# RF_ADF.net
KiCad netlist of a schematic drawn in Altium Designer
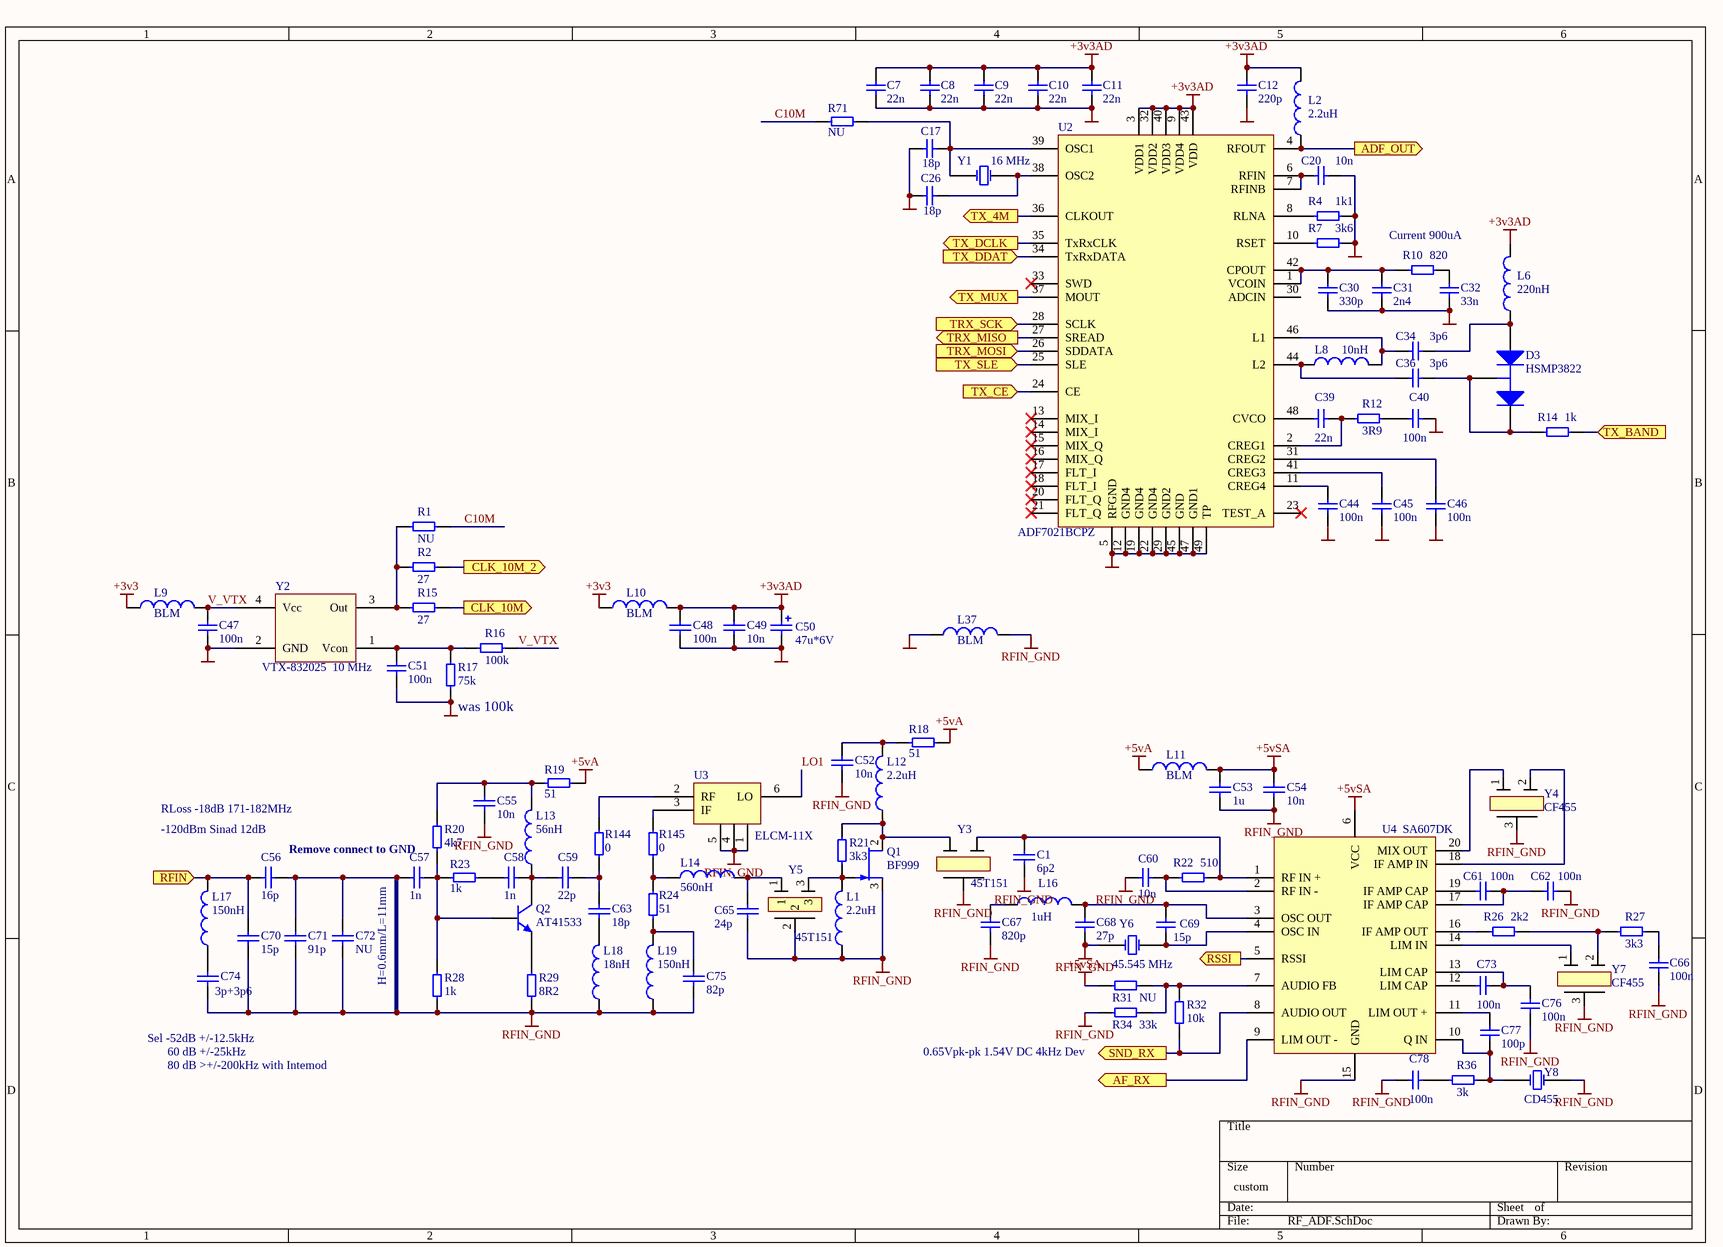
[diagram p0: RF_ADF.SchDoc]

(export (version "E")
  (design (tool "Eeschema 10.0.6"))
  (components
    (comp (ref "C1")
      (value "6p2")
      (footprint "CAPC2012N")
      (description "Capacitor")
      (fields (field (name "PUBLISHER") "Altium Limited"))
      (libsource (lib "Sch components") (part "Cap"))
    )
    (comp (ref "C7")
      (value "22n")
      (footprint "CAPC1608L")
      (description "Capacitor")
      (fields (field (name "PUBLISHER") "Altium Limited"))
      (libsource (lib "") (part "Cap_1"))
    )
    (comp (ref "C8")
      (value "22n")
      (footprint "CAPC1608L")
      (description "Capacitor")
      (fields (field (name "PUBLISHER") "Altium Limited"))
      (libsource (lib "") (part "Cap_1"))
    )
    (comp (ref "C9")
      (value "22n")
      (footprint "CAPC1608L")
      (description "Capacitor")
      (fields (field (name "PUBLISHER") "Altium Limited"))
      (libsource (lib "") (part "Cap_1"))
    )
    (comp (ref "C10")
      (value "22n")
      (footprint "CAPC1608L")
      (description "Capacitor")
      (fields (field (name "PUBLISHER") "Altium Limited"))
      (libsource (lib "") (part "Cap_1"))
    )
    (comp (ref "C11")
      (value "22n")
      (footprint "CAPC1608L")
      (description "Capacitor")
      (fields (field (name "PUBLISHER") "Altium Limited"))
      (libsource (lib "") (part "Cap_1"))
    )
    (comp (ref "C12")
      (value "220p")
      (footprint "CAPC1608L")
      (description "Capacitor")
      (fields (field (name "PUBLISHER") "Altium Limited"))
      (libsource (lib "") (part "Cap_1"))
    )
    (comp (ref "C17")
      (value "18p")
      (footprint "CAPC1608L")
      (description "Capacitor")
      (fields (field (name "PUBLISHER") "Altium Limited"))
      (libsource (lib "") (part "Cap_1"))
    )
    (comp (ref "C20")
      (value "10n")
      (footprint "CAPC1608L")
      (description "Capacitor")
      (fields (field (name "PUBLISHER") "Altium Limited"))
      (libsource (lib "") (part "Cap_1"))
    )
    (comp (ref "C26")
      (value "18p")
      (footprint "CAPC1608L")
      (description "Capacitor")
      (fields (field (name "PUBLISHER") "Altium Limited"))
      (libsource (lib "") (part "Cap_1"))
    )
    (comp (ref "C30")
      (value "330p")
      (footprint "CAPC1608L")
      (description "Capacitor")
      (fields (field (name "PUBLISHER") "Altium Limited"))
      (libsource (lib "") (part "Cap_1"))
    )
    (comp (ref "C31")
      (value "2n4")
      (footprint "CAPC1608L")
      (description "Capacitor")
      (fields (field (name "PUBLISHER") "Altium Limited"))
      (libsource (lib "") (part "Cap_1"))
    )
    (comp (ref "C32")
      (value "33n")
      (footprint "CAPC1608L")
      (description "Capacitor")
      (fields (field (name "PUBLISHER") "Altium Limited"))
      (libsource (lib "") (part "Cap_1"))
    )
    (comp (ref "C34")
      (value "3p6")
      (footprint "CAPC1608L")
      (description "Capacitor")
      (fields (field (name "PUBLISHER") "Altium Limited"))
      (libsource (lib "") (part "Cap_1"))
    )
    (comp (ref "C36")
      (value "3p6")
      (footprint "CAPC1608L")
      (description "Capacitor")
      (fields (field (name "PUBLISHER") "Altium Limited"))
      (libsource (lib "") (part "Cap_1"))
    )
    (comp (ref "C39")
      (value "22n")
      (footprint "CAPC1608L")
      (description "Capacitor")
      (fields (field (name "PUBLISHER") "Altium Limited"))
      (libsource (lib "") (part "Cap_1"))
    )
    (comp (ref "C40")
      (value "100n")
      (footprint "CAPC1608L")
      (description "Capacitor")
      (fields (field (name "PUBLISHER") "Altium Limited"))
      (libsource (lib "") (part "Cap_1"))
    )
    (comp (ref "C44")
      (value "100n")
      (footprint "CAPC1608L")
      (description "Capacitor")
      (fields (field (name "PUBLISHER") "Altium Limited"))
      (libsource (lib "") (part "Cap_1"))
    )
    (comp (ref "C45")
      (value "100n")
      (footprint "CAPC1608L")
      (description "Capacitor")
      (fields (field (name "PUBLISHER") "Altium Limited"))
      (libsource (lib "") (part "Cap_1"))
    )
    (comp (ref "C46")
      (value "100n")
      (footprint "CAPC1608L")
      (description "Capacitor")
      (fields (field (name "PUBLISHER") "Altium Limited"))
      (libsource (lib "") (part "Cap_1"))
    )
    (comp (ref "C47")
      (value "100n")
      (footprint "CAPC1608L")
      (description "Capacitor")
      (fields (field (name "PUBLISHER") "Altium Limited"))
      (libsource (lib "") (part "Cap_1"))
    )
    (comp (ref "C48")
      (value "100n")
      (footprint "CAPC1608N")
      (description "Capacitor")
      (fields (field (name "PUBLISHER") "Altium Limited"))
      (libsource (lib "Sch components") (part "Cap"))
    )
    (comp (ref "C49")
      (value "10n")
      (footprint "CAPC1608N")
      (description "Capacitor")
      (fields (field (name "PUBLISHER") "Altium Limited"))
      (libsource (lib "Sch components") (part "Cap"))
    )
    (comp (ref "C50")
      (value "47u*6V")
      (footprint "Case_A")
      (description "Polarized Capacitor (Surface Mount)")
      (fields (field (name "PUBLISHER") "Altium Limited"))
      (libsource (lib "Sch components") (part "Cap Pol"))
    )
    (comp (ref "C51")
      (value "100n")
      (footprint "CAPC1608L")
      (description "Capacitor")
      (fields (field (name "PUBLISHER") "Altium Limited"))
      (libsource (lib "") (part "Cap_1"))
    )
    (comp (ref "C52")
      (value "10n")
      (footprint "CAPC2012N")
      (description "Capacitor")
      (fields (field (name "PUBLISHER") "Altium Limited"))
      (libsource (lib "Sch components") (part "Cap"))
    )
    (comp (ref "C53")
      (value "1u")
      (footprint "CAPC2012L")
      (description "Capacitor")
      (fields (field (name "PUBLISHER") "Altium Limited"))
      (libsource (lib "Sch components") (part "Cap"))
    )
    (comp (ref "C54")
      (value "10n")
      (footprint "CAPC1608L")
      (description "Capacitor")
      (fields (field (name "PUBLISHER") "Altium Limited"))
      (libsource (lib "Sch components") (part "Cap"))
    )
    (comp (ref "C55")
      (value "10n")
      (footprint "CAPC2012N")
      (description "Capacitor")
      (fields (field (name "PUBLISHER") "Altium Limited"))
      (libsource (lib "Sch components") (part "Cap"))
    )
    (comp (ref "C56")
      (value "16p")
      (footprint "CAPC2012N")
      (description "Capacitor")
      (fields (field (name "PUBLISHER") "Altium Limited"))
      (libsource (lib "Sch components") (part "Cap"))
    )
    (comp (ref "C57")
      (value "1n")
      (footprint "CAPC2012N")
      (description "Capacitor")
      (fields (field (name "PUBLISHER") "Altium Limited"))
      (libsource (lib "Sch components") (part "Cap"))
    )
    (comp (ref "C58")
      (value "1n")
      (footprint "CAPC2012N")
      (description "Capacitor")
      (fields (field (name "PUBLISHER") "Altium Limited"))
      (libsource (lib "Sch components") (part "Cap"))
    )
    (comp (ref "C59")
      (value "22p")
      (footprint "CAPC2012N")
      (description "Capacitor")
      (fields (field (name "PUBLISHER") "Altium Limited"))
      (libsource (lib "Sch components") (part "Cap"))
    )
    (comp (ref "C60")
      (value "10n")
      (footprint "CAPC1608L")
      (description "Capacitor")
      (fields (field (name "PUBLISHER") "Altium Limited"))
      (libsource (lib "") (part "Cap_1"))
    )
    (comp (ref "C61")
      (value "100n")
      (footprint "CAPC1608L")
      (description "Capacitor")
      (fields (field (name "PUBLISHER") "Altium Limited"))
      (libsource (lib "") (part "Cap_1"))
    )
    (comp (ref "C62")
      (value "100n")
      (footprint "CAPC1608L")
      (description "Capacitor")
      (fields (field (name "PUBLISHER") "Altium Limited"))
      (libsource (lib "") (part "Cap_1"))
    )
    (comp (ref "C63")
      (value "18p")
      (footprint "CAPC2012N")
      (description "Capacitor")
      (fields (field (name "PUBLISHER") "Altium Limited"))
      (libsource (lib "Sch components") (part "Cap"))
    )
    (comp (ref "C65")
      (value "24p")
      (footprint "CAPC2012N")
      (description "Capacitor")
      (fields (field (name "PUBLISHER") "Altium Limited"))
      (libsource (lib "Sch components") (part "Cap"))
    )
    (comp (ref "C66")
      (value "100n")
      (footprint "CAPC1608L")
      (description "Capacitor")
      (fields (field (name "PUBLISHER") "Altium Limited"))
      (libsource (lib "") (part "Cap_1"))
    )
    (comp (ref "C67")
      (value "820p")
      (footprint "CAPC1608L")
      (description "Capacitor")
      (fields (field (name "PUBLISHER") "Altium Limited"))
      (libsource (lib "") (part "Cap_1"))
    )
    (comp (ref "C68")
      (value "27p")
      (footprint "CAPC1608L")
      (description "Capacitor")
      (fields (field (name "PUBLISHER") "Altium Limited"))
      (libsource (lib "") (part "Cap_1"))
    )
    (comp (ref "C69")
      (value "15p")
      (footprint "CAPC1608L")
      (description "Capacitor")
      (fields (field (name "PUBLISHER") "Altium Limited"))
      (libsource (lib "") (part "Cap_1"))
    )
    (comp (ref "C70")
      (value "15p")
      (footprint "CAPC2012N")
      (description "Capacitor")
      (fields (field (name "PUBLISHER") "Altium Limited"))
      (libsource (lib "Sch components") (part "Cap"))
    )
    (comp (ref "C71")
      (value "91p")
      (footprint "CAPC2012N")
      (description "Capacitor")
      (fields (field (name "PUBLISHER") "Altium Limited"))
      (libsource (lib "Sch components") (part "Cap"))
    )
    (comp (ref "C72")
      (value "NU")
      (footprint "CAPC2012N")
      (description "Capacitor")
      (fields (field (name "PUBLISHER") "Altium Limited"))
      (libsource (lib "Sch components") (part "Cap"))
    )
    (comp (ref "C73")
      (value "100n")
      (footprint "CAPC1608L")
      (description "Capacitor")
      (fields (field (name "PUBLISHER") "Altium Limited"))
      (libsource (lib "") (part "Cap_1"))
    )
    (comp (ref "C74")
      (value "3p+3p6")
      (footprint "CAPC2012N")
      (description "Capacitor")
      (fields (field (name "PUBLISHER") "Altium Limited"))
      (libsource (lib "Sch components") (part "Cap"))
    )
    (comp (ref "C75")
      (value "82p")
      (footprint "CAPC2012N")
      (description "Capacitor")
      (fields (field (name "PUBLISHER") "Altium Limited"))
      (libsource (lib "Sch components") (part "Cap"))
    )
    (comp (ref "C76")
      (value "100n")
      (footprint "CAPC1608L")
      (description "Capacitor")
      (fields (field (name "PUBLISHER") "Altium Limited"))
      (libsource (lib "") (part "Cap_1"))
    )
    (comp (ref "C77")
      (value "100p")
      (footprint "CAPC1608L")
      (description "Capacitor")
      (fields (field (name "PUBLISHER") "Altium Limited"))
      (libsource (lib "") (part "Cap_1"))
    )
    (comp (ref "C78")
      (value "100n")
      (footprint "CAPC1608L")
      (description "Capacitor")
      (fields (field (name "PUBLISHER") "Altium Limited"))
      (libsource (lib "") (part "Cap_1"))
    )
    (comp (ref "D3")
      (value "HSMP3822")
      (footprint "SOT-23")
      (description "Silicon Switching Diode Array for High-Speed Switching")
      (fields (field (name "PUBLISHER") "Altium Limited"))
      (libsource (lib "Infineon Discrete Diode") (part "SMBD7000"))
    )
    (comp (ref "L1")
      (value "2.2uH")
      (footprint "INDC2012N")
      (description "Inductor")
      (fields (field (name "PUBLISHER") "Altium Limited"))
      (libsource (lib "Sch components") (part "Inductor"))
    )
    (comp (ref "L2") (value "2.2uH") (footprint "INDC2012L") (libsource (lib "MyLibrary") (part "INDUCTOR")))
    (comp (ref "L6") (value "220nH") (footprint "INDC2012L") (libsource (lib "MyLibrary") (part "INDUCTOR")))
    (comp (ref "L8") (value "10nH") (footprint "INDC2012L") (libsource (lib "MyLibrary") (part "INDUCTOR")))
    (comp (ref "L9")
      (value "BLM")
      (footprint "CAPC2012N")
      (description "Ferrite Bead")
      (fields (field (name "PUBLISHER") "Altium Limited"))
      (libsource (lib "Sch components") (part "Ferrite Bead"))
    )
    (comp (ref "L10")
      (value "BLM")
      (footprint "CAPC2012N")
      (description "Ferrite Bead")
      (fields (field (name "PUBLISHER") "Altium Limited"))
      (libsource (lib "Sch components") (part "Ferrite Bead"))
    )
    (comp (ref "L11")
      (value "BLM")
      (footprint "CAPC2012N")
      (description "Ferrite Bead")
      (fields (field (name "PUBLISHER") "Altium Limited"))
      (libsource (lib "Sch components") (part "Ferrite Bead"))
    )
    (comp (ref "L12")
      (value "2.2uH")
      (footprint "INDC2012N")
      (description "Inductor")
      (fields (field (name "PUBLISHER") "Altium Limited"))
      (libsource (lib "Sch components") (part "Inductor"))
    )
    (comp (ref "L13")
      (value "56nH")
      (footprint "INDC2012N")
      (description "Inductor")
      (fields (field (name "PUBLISHER") "Altium Limited"))
      (libsource (lib "Sch components") (part "Inductor"))
    )
    (comp (ref "L14")
      (value "560nH")
      (footprint "INDC2012N")
      (description "Inductor")
      (fields (field (name "PUBLISHER") "Altium Limited"))
      (libsource (lib "Sch components") (part "Inductor"))
    )
    (comp (ref "L16") (value "1uH") (footprint "INDC2012L") (libsource (lib "MyLibrary") (part "INDUCTOR")))
    (comp (ref "L17")
      (value "150nH")
      (footprint "INDC2012N")
      (description "Inductor")
      (fields (field (name "PUBLISHER") "Altium Limited"))
      (libsource (lib "Sch components") (part "Inductor"))
    )
    (comp (ref "L18")
      (value "18nH")
      (footprint "INDC2012N")
      (description "Inductor")
      (fields (field (name "PUBLISHER") "Altium Limited"))
      (libsource (lib "Sch components") (part "Inductor"))
    )
    (comp (ref "L19")
      (value "150nH")
      (footprint "INDC2012N")
      (description "Inductor")
      (fields (field (name "PUBLISHER") "Altium Limited"))
      (libsource (lib "Sch components") (part "Inductor"))
    )
    (comp (ref "L37")
      (value "BLM")
      (footprint "CAPC2012N")
      (description "Ferrite Bead")
      (fields (field (name "PUBLISHER") "Altium Limited"))
      (libsource (lib "Sch components") (part "Ferrite Bead"))
    )
    (comp (ref "Q1")
      (value "BF999")
      (footprint "sot23_n")
      (description "N-channel Silicon Junction Field-effect Transistor")
      (fields (field (name "PUBLISHER") "Altium Limited"))
      (libsource (lib "Sch components") (part "BF999"))
    )
    (comp (ref "Q2")
      (value "AT41533")
      (footprint "SOT-23")
      (description "NPN 5 GHz Wideband Transistor")
      (fields (field (name "PUBLISHER") "Altium Limited"))
      (libsource (lib "Philips Discrete BJT - RF Transistor") (part "BFR92A"))
    )
    (comp (ref "R1")
      (value "NU")
      (footprint "RESC1608L")
      (description "Resistor")
      (fields (field (name "PUBLISHER") "Altium Limited"))
      (libsource (lib "Sch components") (part "Res"))
    )
    (comp (ref "R2")
      (value "27")
      (footprint "RESC1608L")
      (description "Resistor")
      (fields (field (name "PUBLISHER") "Altium Limited"))
      (libsource (lib "Sch components") (part "Res"))
    )
    (comp (ref "R4")
      (value "1k1")
      (footprint "RESC1608L")
      (description "Resistor")
      (fields (field (name "PUBLISHER") "Altium Limited"))
      (libsource (lib "Sch components") (part "Res"))
    )
    (comp (ref "R7")
      (value "3k6")
      (footprint "RESC1608L")
      (description "Resistor")
      (fields (field (name "PUBLISHER") "Altium Limited"))
      (libsource (lib "Sch components") (part "Res"))
    )
    (comp (ref "R10")
      (value "820")
      (footprint "RESC1608L")
      (description "Resistor")
      (fields (field (name "PUBLISHER") "Altium Limited"))
      (libsource (lib "Sch components") (part "Res"))
    )
    (comp (ref "R12")
      (value "3R9")
      (footprint "RESC1608L")
      (description "Resistor")
      (fields (field (name "PUBLISHER") "Altium Limited"))
      (libsource (lib "Sch components") (part "Res"))
    )
    (comp (ref "R14")
      (value "1k")
      (footprint "RESC1608L")
      (description "Resistor")
      (fields (field (name "PUBLISHER") "Altium Limited"))
      (libsource (lib "Sch components") (part "Res"))
    )
    (comp (ref "R15")
      (value "27")
      (footprint "RESC1608L")
      (description "Resistor")
      (fields (field (name "PUBLISHER") "Altium Limited"))
      (libsource (lib "Sch components") (part "Res"))
    )
    (comp (ref "R16")
      (value "100k")
      (footprint "RESC1608L")
      (description "Resistor")
      (fields (field (name "PUBLISHER") "Altium Limited"))
      (libsource (lib "Sch components") (part "Res"))
    )
    (comp (ref "R17")
      (value "75k")
      (footprint "RESC1608L")
      (description "Resistor")
      (fields (field (name "PUBLISHER") "Altium Limited"))
      (libsource (lib "Sch components") (part "Res"))
    )
    (comp (ref "R18")
      (value "51")
      (footprint "RESC2012N")
      (description "Resistor")
      (fields (field (name "PUBLISHER") "Altium Limited"))
      (libsource (lib "Sch components") (part "Res"))
    )
    (comp (ref "R19")
      (value "51")
      (footprint "RESC2012N")
      (description "Resistor")
      (fields (field (name "PUBLISHER") "Altium Limited"))
      (libsource (lib "Sch components") (part "Res"))
    )
    (comp (ref "R20")
      (value "4k7")
      (footprint "RESC2012N")
      (description "Resistor")
      (fields (field (name "PUBLISHER") "Altium Limited"))
      (libsource (lib "Sch components") (part "Res"))
    )
    (comp (ref "R21")
      (value "3k3")
      (footprint "RESC2012N")
      (description "Resistor")
      (fields (field (name "PUBLISHER") "Altium Limited"))
      (libsource (lib "Sch components") (part "Res"))
    )
    (comp (ref "R22")
      (value "510")
      (footprint "RESC1608L")
      (description "Resistor")
      (fields (field (name "PUBLISHER") "Altium Limited"))
      (libsource (lib "Sch components") (part "Res"))
    )
    (comp (ref "R23")
      (value "1k")
      (footprint "RESC2012N")
      (description "Resistor")
      (fields (field (name "PUBLISHER") "Altium Limited"))
      (libsource (lib "Sch components") (part "Res"))
    )
    (comp (ref "R24")
      (value "51")
      (footprint "RESC2012N")
      (description "Resistor")
      (fields (field (name "PUBLISHER") "Altium Limited"))
      (libsource (lib "Sch components") (part "Res"))
    )
    (comp (ref "R26")
      (value "2k2")
      (footprint "RESC1608L")
      (description "Resistor")
      (fields (field (name "PUBLISHER") "Altium Limited"))
      (libsource (lib "Sch components") (part "Res"))
    )
    (comp (ref "R27")
      (value "3k3")
      (footprint "RESC1608L")
      (description "Resistor")
      (fields (field (name "PUBLISHER") "Altium Limited"))
      (libsource (lib "Sch components") (part "Res"))
    )
    (comp (ref "R28")
      (value "1k")
      (footprint "RESC2012N")
      (description "Resistor")
      (fields (field (name "PUBLISHER") "Altium Limited"))
      (libsource (lib "Sch components") (part "Res"))
    )
    (comp (ref "R29")
      (value "8R2")
      (footprint "RESC2012N")
      (description "Resistor")
      (fields (field (name "PUBLISHER") "Altium Limited"))
      (libsource (lib "Sch components") (part "Res"))
    )
    (comp (ref "R31")
      (value "NU")
      (footprint "RESC1608L")
      (description "Resistor")
      (fields (field (name "PUBLISHER") "Altium Limited"))
      (libsource (lib "Sch components") (part "Res"))
    )
    (comp (ref "R32")
      (value "10k")
      (footprint "RESC1608L")
      (description "Resistor")
      (fields (field (name "PUBLISHER") "Altium Limited"))
      (libsource (lib "Sch components") (part "Res"))
    )
    (comp (ref "R34")
      (value "33k")
      (footprint "RESC1608L")
      (description "Resistor")
      (fields (field (name "PUBLISHER") "Altium Limited"))
      (libsource (lib "Sch components") (part "Res"))
    )
    (comp (ref "R36")
      (value "3k")
      (footprint "RESC1608L")
      (description "Resistor")
      (fields (field (name "PUBLISHER") "Altium Limited"))
      (libsource (lib "Sch components") (part "Res"))
    )
    (comp (ref "R71")
      (value "NU")
      (footprint "RESC1608L")
      (description "Resistor")
      (fields (field (name "PUBLISHER") "Altium Limited"))
      (libsource (lib "Sch components") (part "Res"))
    )
    (comp (ref "R144")
      (value "0")
      (footprint "RESC1608L")
      (description "Resistor")
      (fields (field (name "PUBLISHER") "Altium Limited"))
      (libsource (lib "Sch components") (part "Res"))
    )
    (comp (ref "R145")
      (value "0")
      (footprint "RESC1608L")
      (description "Resistor")
      (fields (field (name "PUBLISHER") "Altium Limited"))
      (libsource (lib "Sch components") (part "Res"))
    )
    (comp (ref "U2")
      (value "ADF7021BCPZ")
      (footprint "QFN50P700X700X100-49N")
      (description "ISM Band, FSK/ASK Tranceiver IC")
      (libsource (lib "Sch components") (part "ADF7021"))
    )
    (comp (ref "U3")
      (value "ELCM-11X")
      (footprint "ELCM-11X")
      (description "Broadband mixer")
      (libsource (lib "Sch components") (part "ELCM-11X"))
    )
    (comp (ref "U4")
      (value "SA607DK")
      (footprint "SOT266-1")
      (description "Low-voltage high perfomance mixer FM IF system")
      (libsource (lib "Sch components") (part "SA607"))
    )
    (comp (ref "Y1")
      (value "16 MHz")
      (footprint "NX3225A")
      (description "Crystal Oscillator")
      (fields (field (name "PUBLISHER") "Altium Limited"))
      (libsource (lib "Sch components") (part "XTAL"))
    )
    (comp (ref "Y2")
      (value "VTX-832025  10 MHz")
      (footprint "SMD3.2x5")
      (libsource (lib "MyWLib") (part "KT18B-DCU28B"))
    )
    (comp (ref "Y3")
      (value "45T151")
      (footprint "45T151AF")
      (description "10.7 IF Filter")
      (libsource (lib "") (part "SFE10.7MS3_2"))
    )
    (comp (ref "Y4")
      (value "CF455")
      (footprint "CFUCG455G")
      (description "455k IF Filter")
      (libsource (lib "Sch components") (part "SFE10.7MS3"))
    )
    (comp (ref "Y5")
      (value "45T151")
      (footprint "45T151AF")
      (description "10.7 IF Filter")
      (libsource (lib "") (part "SFE10.7MS3_1"))
    )
    (comp (ref "Y6")
      (value "45.545 MHz")
      (footprint "SIWARD UM-58")
      (description "Crystal Oscillator")
      (fields (field (name "PUBLISHER") "Altium Limited"))
      (libsource (lib "Sch components") (part "XTAL"))
    )
    (comp (ref "Y7")
      (value "CF455")
      (footprint "CFUCG455G")
      (description "455k IF Filter")
      (libsource (lib "Sch components") (part "SFE10.7MS3"))
    )
    (comp (ref "Y8")
      (value "CD455")
      (footprint "CDBC455CLX1")
      (description "455k Discriminator")
      (fields (field (name "PUBLISHER") "Altium Limited"))
      (libsource (lib "Sch components") (part "XTAL"))
    )
  )
  (nets
    (net (code "1") (name "+3v3") (class "Default")
      (node (ref "L10") (pin "1") (pinfunction "1_1") (pintype "passive"))
      (node (ref "L9") (pin "1") (pinfunction "1_1") (pintype "passive"))
    )
    (net (code "2") (name "+3v3AD") (class "Default")
      (node (ref "C10") (pin "1") (pinfunction "1_1") (pintype "passive"))
      (node (ref "C11") (pin "1") (pinfunction "1_1") (pintype "passive"))
      (node (ref "C12") (pin "1") (pinfunction "1_1") (pintype "passive"))
      (node (ref "C48") (pin "2") (pinfunction "2_2") (pintype "passive"))
      (node (ref "C49") (pin "2") (pinfunction "2_2") (pintype "passive"))
      (node (ref "C50") (pin "1") (pinfunction "1_1") (pintype "passive"))
      (node (ref "C7") (pin "1") (pinfunction "1_1") (pintype "passive"))
      (node (ref "C8") (pin "1") (pinfunction "1_1") (pintype "passive"))
      (node (ref "C9") (pin "1") (pinfunction "1_1") (pintype "passive"))
      (node (ref "L10") (pin "2") (pinfunction "2_2") (pintype "passive"))
      (node (ref "L2") (pin "2") (pinfunction "2_2") (pintype "passive"))
      (node (ref "L6") (pin "2") (pinfunction "2_2") (pintype "passive"))
      (node (ref "U2") (pin "3") (pinfunction "VDD1_3") (pintype "passive"))
      (node (ref "U2") (pin "32") (pinfunction "VDD2_32") (pintype "passive"))
      (node (ref "U2") (pin "40") (pinfunction "VDD3_40") (pintype "passive"))
      (node (ref "U2") (pin "43") (pinfunction "VDD_43") (pintype "passive"))
      (node (ref "U2") (pin "9") (pinfunction "VDD4_9") (pintype "passive"))
    )
    (net (code "3") (name "+5vA") (class "Default")
      (node (ref "L11") (pin "1") (pinfunction "1_1") (pintype "passive"))
      (node (ref "R18") (pin "2") (pinfunction "2_2") (pintype "passive"))
      (node (ref "R19") (pin "2") (pinfunction "2_2") (pintype "passive"))
    )
    (net (code "4") (name "+5vSA") (class "Default")
      (node (ref "C53") (pin "2") (pinfunction "2_2") (pintype "passive"))
      (node (ref "C54") (pin "2") (pinfunction "2_2") (pintype "passive"))
      (node (ref "L11") (pin "2") (pinfunction "2_2") (pintype "passive"))
      (node (ref "R31") (pin "2") (pinfunction "2_2") (pintype "passive"))
      (node (ref "U4") (pin "6") (pinfunction "VCC_6") (pintype "passive"))
    )
    (net (code "5") (name "/ADF_OUT") (class "Default")
      (node (ref "L2") (pin "1") (pinfunction "1_1") (pintype "passive"))
      (node (ref "U2") (pin "4") (pinfunction "RFOUT_4") (pintype "passive"))
    )
    (net (code "6") (name "/AF_RX") (class "Default")
      (node (ref "U4") (pin "9") (pinfunction "LIM_OUT_-_9") (pintype "passive"))
    )
    (net (code "7") (name "/C10M") (class "Default")
      (node (ref "R1") (pin "1") (pinfunction "1_1") (pintype "passive"))
      (node (ref "R71") (pin "1") (pinfunction "1_1") (pintype "passive"))
    )
    (net (code "8") (name "/CLK_10M") (class "Default")
      (node (ref "R15") (pin "1") (pinfunction "1_1") (pintype "passive"))
    )
    (net (code "9") (name "/CLK_10M_2") (class "Default")
      (node (ref "R2") (pin "1") (pinfunction "1_1") (pintype "passive"))
    )
    (net (code "10") (name "/LO1") (class "Default")
      (node (ref "U3") (pin "6") (pinfunction "LO_6") (pintype "passive"))
    )
    (net (code "11") (name "/RFIN") (class "Default")
      (node (ref "C56") (pin "2") (pinfunction "2_2") (pintype "passive"))
      (node (ref "C70") (pin "2") (pinfunction "2_2") (pintype "passive"))
      (node (ref "L17") (pin "2") (pinfunction "2_2") (pintype "passive"))
    )
    (net (code "12") (name "/RSSI") (class "Default")
      (node (ref "U4") (pin "5") (pinfunction "RSSI_5") (pintype "passive"))
    )
    (net (code "13") (name "/SND_RX") (class "Default")
      (node (ref "R32") (pin "2") (pinfunction "2_2") (pintype "passive"))
      (node (ref "U4") (pin "8") (pinfunction "AUDIO_OUT_8") (pintype "passive"))
    )
    (net (code "14") (name "/TRX_MISO") (class "Default")
      (node (ref "U2") (pin "27") (pinfunction "SREAD_27") (pintype "passive"))
    )
    (net (code "15") (name "/TRX_MOSI") (class "Default")
      (node (ref "U2") (pin "26") (pinfunction "SDDATA_26") (pintype "passive"))
    )
    (net (code "16") (name "/TRX_SCK") (class "Default")
      (node (ref "U2") (pin "28") (pinfunction "SCLK_28") (pintype "passive"))
    )
    (net (code "17") (name "/TX_4M") (class "Default")
      (node (ref "U2") (pin "36") (pinfunction "CLKOUT_36") (pintype "passive"))
    )
    (net (code "18") (name "/TX_BAND") (class "Default")
      (node (ref "R14") (pin "1") (pinfunction "1_1") (pintype "passive"))
    )
    (net (code "19") (name "/TX_CE") (class "Default")
      (node (ref "U2") (pin "24") (pinfunction "CE_24") (pintype "passive"))
    )
    (net (code "20") (name "/TX_DCLK") (class "Default")
      (node (ref "U2") (pin "35") (pinfunction "TxRxCLK_35") (pintype "passive"))
    )
    (net (code "21") (name "/TX_DDAT") (class "Default")
      (node (ref "U2") (pin "34") (pinfunction "TxRxDATA_34") (pintype "passive"))
    )
    (net (code "22") (name "/TX_MUX") (class "Default")
      (node (ref "U2") (pin "37") (pinfunction "MOUT_37") (pintype "passive"))
    )
    (net (code "23") (name "/TX_SLE") (class "Default")
      (node (ref "U2") (pin "25") (pinfunction "SLE_25") (pintype "passive"))
    )
    (net (code "24") (name "/V_VTX") (class "Default")
      (node (ref "C47") (pin "1") (pinfunction "1_1") (pintype "passive"))
      (node (ref "L9") (pin "2") (pinfunction "2_2") (pintype "passive"))
      (node (ref "R16") (pin "1") (pinfunction "1_1") (pintype "passive"))
      (node (ref "Y2") (pin "4") (pinfunction "Vcc_4") (pintype "passive"))
    )
    (net (code "25") (name "GND") (class "Default")
      (node (ref "C10") (pin "2") (pinfunction "2_2") (pintype "passive"))
      (node (ref "C11") (pin "2") (pinfunction "2_2") (pintype "passive"))
      (node (ref "C12") (pin "2") (pinfunction "2_2") (pintype "passive"))
      (node (ref "C17") (pin "1") (pinfunction "1_1") (pintype "passive"))
      (node (ref "C20") (pin "1") (pinfunction "1_1") (pintype "passive"))
      (node (ref "C26") (pin "2") (pinfunction "2_2") (pintype "passive"))
      (node (ref "C30") (pin "2") (pinfunction "2_2") (pintype "passive"))
      (node (ref "C31") (pin "2") (pinfunction "2_2") (pintype "passive"))
      (node (ref "C32") (pin "2") (pinfunction "2_2") (pintype "passive"))
      (node (ref "C40") (pin "1") (pinfunction "1_1") (pintype "passive"))
      (node (ref "C44") (pin "2") (pinfunction "2_2") (pintype "passive"))
      (node (ref "C45") (pin "2") (pinfunction "2_2") (pintype "passive"))
      (node (ref "C46") (pin "2") (pinfunction "2_2") (pintype "passive"))
      (node (ref "C47") (pin "2") (pinfunction "2_2") (pintype "passive"))
      (node (ref "C48") (pin "1") (pinfunction "1_1") (pintype "passive"))
      (node (ref "C49") (pin "1") (pinfunction "1_1") (pintype "passive"))
      (node (ref "C50") (pin "2") (pinfunction "2_2") (pintype "passive"))
      (node (ref "C51") (pin "2") (pinfunction "2_2") (pintype "passive"))
      (node (ref "C7") (pin "2") (pinfunction "2_2") (pintype "passive"))
      (node (ref "C8") (pin "2") (pinfunction "2_2") (pintype "passive"))
      (node (ref "C9") (pin "2") (pinfunction "2_2") (pintype "passive"))
      (node (ref "L37") (pin "1") (pinfunction "1_1") (pintype "passive"))
      (node (ref "R17") (pin "2") (pinfunction "2_2") (pintype "passive"))
      (node (ref "R4") (pin "1") (pinfunction "1_1") (pintype "passive"))
      (node (ref "R7") (pin "1") (pinfunction "1_1") (pintype "passive"))
      (node (ref "U2") (pin "12") (pinfunction "GND4_12") (pintype "passive"))
      (node (ref "U2") (pin "19") (pinfunction "GND4_19") (pintype "passive"))
      (node (ref "U2") (pin "22") (pinfunction "GND4_22") (pintype "passive"))
      (node (ref "U2") (pin "29") (pinfunction "GND2_29") (pintype "passive"))
      (node (ref "U2") (pin "45") (pinfunction "GND_45") (pintype "passive"))
      (node (ref "U2") (pin "47") (pinfunction "GND1_47") (pintype "passive"))
      (node (ref "U2") (pin "49") (pinfunction "TP_49") (pintype "passive"))
      (node (ref "U2") (pin "5") (pinfunction "RFGND_5") (pintype "passive"))
      (node (ref "Y2") (pin "2") (pinfunction "GND_2") (pintype "passive"))
    )
    (net (code "26") (name "Net-(C32-Pad1)") (class "Default")
      (node (ref "C32") (pin "1") (pinfunction "1_1") (pintype "passive"))
      (node (ref "R10") (pin "1") (pinfunction "1_1") (pintype "passive"))
    )
    (net (code "27") (name "Net-(C40-Pad2)") (class "Default")
      (node (ref "C40") (pin "2") (pinfunction "2_2") (pintype "passive"))
      (node (ref "R12") (pin "1") (pinfunction "1_1") (pintype "passive"))
    )
    (net (code "28") (name "Net-(C52-Pad2)") (class "Default")
      (node (ref "C52") (pin "2") (pinfunction "2_2") (pintype "passive"))
      (node (ref "L12") (pin "2") (pinfunction "2_2") (pintype "passive"))
      (node (ref "R18") (pin "1") (pinfunction "1_1") (pintype "passive"))
    )
    (net (code "29") (name "Net-(C55-Pad2)") (class "Default")
      (node (ref "C55") (pin "2") (pinfunction "2_2") (pintype "passive"))
      (node (ref "L13") (pin "2") (pinfunction "2_2") (pintype "passive"))
      (node (ref "R19") (pin "1") (pinfunction "1_1") (pintype "passive"))
      (node (ref "R20") (pin "1") (pinfunction "1_1") (pintype "passive"))
    )
    (net (code "30") (name "Net-(C58-Pad2)") (class "Default")
      (node (ref "C58") (pin "2") (pinfunction "2_2") (pintype "passive"))
      (node (ref "R23") (pin "2") (pinfunction "2_2") (pintype "passive"))
    )
    (net (code "31") (name "Net-(C59-Pad1)") (class "Default")
      (node (ref "C59") (pin "1") (pinfunction "1_1") (pintype "passive"))
      (node (ref "C63") (pin "2") (pinfunction "2_2") (pintype "passive"))
      (node (ref "R144") (pin "2") (pinfunction "2_2") (pintype "passive"))
    )
    (net (code "32") (name "Net-(C61-Pad1)") (class "Default")
      (node (ref "C61") (pin "1") (pinfunction "1_1") (pintype "passive"))
      (node (ref "U4") (pin "19") (pinfunction "IF_AMP_CAP_19") (pintype "passive"))
    )
    (net (code "33") (name "Net-(C61-Pad2)") (class "Default")
      (node (ref "C61") (pin "2") (pinfunction "2_2") (pintype "passive"))
      (node (ref "C62") (pin "1") (pinfunction "1_1") (pintype "passive"))
      (node (ref "U4") (pin "17") (pinfunction "IF_AMP_CAP_17") (pintype "passive"))
    )
    (net (code "34") (name "Net-(C63-Pad1)") (class "Default")
      (node (ref "C63") (pin "1") (pinfunction "1_1") (pintype "passive"))
      (node (ref "L18") (pin "2") (pinfunction "2_2") (pintype "passive"))
    )
    (net (code "35") (name "Net-(C65-Pad2)") (class "Default")
      (node (ref "C65") (pin "2") (pinfunction "2_2") (pintype "passive"))
      (node (ref "L14") (pin "2") (pinfunction "2_2") (pintype "passive"))
      (node (ref "Y5") (pin "1") (pinfunction "1_1") (pintype "passive"))
    )
    (net (code "36") (name "Net-(C66-Pad1)") (class "Default")
      (node (ref "C66") (pin "1") (pinfunction "1_1") (pintype "passive"))
      (node (ref "R27") (pin "1") (pinfunction "1_1") (pintype "passive"))
    )
    (net (code "37") (name "Net-(C67-Pad2)") (class "Default")
      (node (ref "C67") (pin "2") (pinfunction "2_2") (pintype "passive"))
      (node (ref "L16") (pin "1") (pinfunction "1_1") (pintype "passive"))
    )
    (net (code "38") (name "Net-(C73-Pad1)") (class "Default")
      (node (ref "C73") (pin "1") (pinfunction "1_1") (pintype "passive"))
      (node (ref "U4") (pin "12") (pinfunction "LIM_CAP_12") (pintype "passive"))
    )
    (net (code "39") (name "Net-(C73-Pad2)") (class "Default")
      (node (ref "C73") (pin "2") (pinfunction "2_2") (pintype "passive"))
      (node (ref "C76") (pin "2") (pinfunction "2_2") (pintype "passive"))
      (node (ref "U4") (pin "13") (pinfunction "LIM_CAP_13") (pintype "passive"))
    )
    (net (code "40") (name "Net-(C74-Pad2)") (class "Default")
      (node (ref "C74") (pin "2") (pinfunction "2_2") (pintype "passive"))
      (node (ref "L17") (pin "1") (pinfunction "1_1") (pintype "passive"))
    )
    (net (code "41") (name "Net-(C75-Pad2)") (class "Default")
      (node (ref "C75") (pin "2") (pinfunction "2_2") (pintype "passive"))
      (node (ref "L19") (pin "2") (pinfunction "2_2") (pintype "passive"))
      (node (ref "R24") (pin "2") (pinfunction "2_2") (pintype "passive"))
    )
    (net (code "42") (name "Net-(C78-Pad2)") (class "Default")
      (node (ref "C78") (pin "2") (pinfunction "2_2") (pintype "passive"))
      (node (ref "R36") (pin "2") (pinfunction "2_2") (pintype "passive"))
    )
    (net (code "43") (name "Net-(D3-A)") (class "Default")
      (node (ref "C34") (pin "1") (pinfunction "1_1") (pintype "passive"))
      (node (ref "D3") (pin "1") (pinfunction "A_1") (pintype "passive"))
      (node (ref "L6") (pin "1") (pinfunction "1_1") (pintype "passive"))
    )
    (net (code "44") (name "Net-(D3-C)") (class "Default")
      (node (ref "C36") (pin "1") (pinfunction "1_1") (pintype "passive"))
      (node (ref "D3") (pin "2") (pinfunction "K_2") (pintype "passive"))
      (node (ref "D3") (pin "3") (pinfunction "C_3") (pintype "passive"))
      (node (ref "R14") (pin "2") (pinfunction "2_2") (pintype "passive"))
    )
    (net (code "45") (name "Net-(L14-Pad1)") (class "Default")
      (node (ref "L14") (pin "1") (pinfunction "1_1") (pintype "passive"))
      (node (ref "R145") (pin "2") (pinfunction "2_2") (pintype "passive"))
      (node (ref "R24") (pin "1") (pinfunction "1_1") (pintype "passive"))
    )
    (net (code "46") (name "Net-(Q1-D)") (class "Default")
      (node (ref "L12") (pin "1") (pinfunction "1_1") (pintype "passive"))
      (node (ref "Q1") (pin "2") (pinfunction "D_2") (pintype "passive"))
      (node (ref "R21") (pin "1") (pinfunction "1_1") (pintype "passive"))
      (node (ref "Y3") (pin "1") (pinfunction "1_1") (pintype "passive"))
    )
    (net (code "47") (name "Net-(Q1-G)") (class "Default")
      (node (ref "L1") (pin "2") (pinfunction "2_2") (pintype "passive"))
      (node (ref "Q1") (pin "1") (pinfunction "G_1") (pintype "passive"))
      (node (ref "R21") (pin "2") (pinfunction "2_2") (pintype "passive"))
      (node (ref "Y5") (pin "3") (pinfunction "3_3") (pintype "passive"))
    )
    (net (code "48") (name "Net-(Q2-B)") (class "Default")
      (node (ref "C57") (pin "1") (pinfunction "1_1") (pintype "passive"))
      (node (ref "Q2") (pin "1") (pinfunction "B_1") (pintype "passive"))
      (node (ref "R20") (pin "2") (pinfunction "2_2") (pintype "passive"))
      (node (ref "R23") (pin "1") (pinfunction "1_1") (pintype "passive"))
      (node (ref "R28") (pin "1") (pinfunction "1_1") (pintype "passive"))
    )
    (net (code "49") (name "Net-(Q2-C)") (class "Default")
      (node (ref "C58") (pin "1") (pinfunction "1_1") (pintype "passive"))
      (node (ref "C59") (pin "2") (pinfunction "2_2") (pintype "passive"))
      (node (ref "L13") (pin "1") (pinfunction "1_1") (pintype "passive"))
      (node (ref "Q2") (pin "3") (pinfunction "C_3") (pintype "passive"))
    )
    (net (code "50") (name "Net-(Q2-E)") (class "Default")
      (node (ref "Q2") (pin "2") (pinfunction "E_2") (pintype "passive"))
      (node (ref "R29") (pin "1") (pinfunction "1_1") (pintype "passive"))
    )
    (net (code "51") (name "Net-(U2-CPOUT)") (class "Default")
      (node (ref "C30") (pin "1") (pinfunction "1_1") (pintype "passive"))
      (node (ref "C31") (pin "1") (pinfunction "1_1") (pintype "passive"))
      (node (ref "R10") (pin "2") (pinfunction "2_2") (pintype "passive"))
      (node (ref "U2") (pin "1") (pinfunction "VCOIN_1") (pintype "passive"))
      (node (ref "U2") (pin "42") (pinfunction "CPOUT_42") (pintype "passive"))
    )
    (net (code "52") (name "Net-(U2-CREG1)") (class "Default")
      (node (ref "C39") (pin "1") (pinfunction "1_1") (pintype "passive"))
      (node (ref "R12") (pin "2") (pinfunction "2_2") (pintype "passive"))
      (node (ref "U2") (pin "2") (pinfunction "CREG1_2") (pintype "passive"))
    )
    (net (code "53") (name "Net-(U2-CREG2)") (class "Default")
      (node (ref "C46") (pin "1") (pinfunction "1_1") (pintype "passive"))
      (node (ref "U2") (pin "31") (pinfunction "CREG2_31") (pintype "passive"))
    )
    (net (code "54") (name "Net-(U2-CREG3)") (class "Default")
      (node (ref "C45") (pin "1") (pinfunction "1_1") (pintype "passive"))
      (node (ref "U2") (pin "41") (pinfunction "CREG3_41") (pintype "passive"))
    )
    (net (code "55") (name "Net-(U2-CREG4)") (class "Default")
      (node (ref "C44") (pin "1") (pinfunction "1_1") (pintype "passive"))
      (node (ref "U2") (pin "11") (pinfunction "CREG4_11") (pintype "passive"))
    )
    (net (code "56") (name "Net-(U2-CVCO)") (class "Default")
      (node (ref "C39") (pin "2") (pinfunction "2_2") (pintype "passive"))
      (node (ref "U2") (pin "48") (pinfunction "CVCO_48") (pintype "passive"))
    )
    (net (code "57") (name "Net-(U2-L1)") (class "Default")
      (node (ref "C34") (pin "2") (pinfunction "2_2") (pintype "passive"))
      (node (ref "L8") (pin "2") (pinfunction "2_2") (pintype "passive"))
      (node (ref "U2") (pin "46") (pinfunction "L1_46") (pintype "passive"))
    )
    (net (code "58") (name "Net-(U2-L2)") (class "Default")
      (node (ref "C36") (pin "2") (pinfunction "2_2") (pintype "passive"))
      (node (ref "L8") (pin "1") (pinfunction "1_1") (pintype "passive"))
      (node (ref "U2") (pin "44") (pinfunction "L2_44") (pintype "passive"))
    )
    (net (code "59") (name "Net-(U2-OSC1)") (class "Default")
      (node (ref "C17") (pin "2") (pinfunction "2_2") (pintype "passive"))
      (node (ref "R71") (pin "2") (pinfunction "2_2") (pintype "passive"))
      (node (ref "U2") (pin "39") (pinfunction "OSC1_39") (pintype "passive"))
      (node (ref "Y1") (pin "1") (pinfunction "OSC1_1") (pintype "passive"))
    )
    (net (code "60") (name "Net-(U2-OSC2)") (class "Default")
      (node (ref "C26") (pin "1") (pinfunction "1_1") (pintype "passive"))
      (node (ref "U2") (pin "38") (pinfunction "OSC2_38") (pintype "passive"))
      (node (ref "Y1") (pin "2") (pinfunction "OSC2_2") (pintype "passive"))
    )
    (net (code "61") (name "Net-(U2-RFIN)") (class "Default")
      (node (ref "C20") (pin "2") (pinfunction "2_2") (pintype "passive"))
      (node (ref "U2") (pin "6") (pinfunction "RFIN_6") (pintype "passive"))
      (node (ref "U2") (pin "7") (pinfunction "RFINB_7") (pintype "passive"))
    )
    (net (code "62") (name "Net-(U2-RLNA)") (class "Default")
      (node (ref "R4") (pin "2") (pinfunction "2_2") (pintype "passive"))
      (node (ref "U2") (pin "8") (pinfunction "RLNA_8") (pintype "passive"))
    )
    (net (code "63") (name "Net-(U2-RSET)") (class "Default")
      (node (ref "R7") (pin "2") (pinfunction "2_2") (pintype "passive"))
      (node (ref "U2") (pin "10") (pinfunction "RSET_10") (pintype "passive"))
    )
    (net (code "64") (name "Net-(U3-IF)") (class "Default")
      (node (ref "R145") (pin "1") (pinfunction "1_1") (pintype "passive"))
      (node (ref "U3") (pin "3") (pinfunction "IF_3") (pintype "passive"))
    )
    (net (code "65") (name "Net-(U3-RF)") (class "Default")
      (node (ref "R144") (pin "1") (pinfunction "1_1") (pintype "passive"))
      (node (ref "U3") (pin "2") (pinfunction "RF_2") (pintype "passive"))
    )
    (net (code "66") (name "Net-(U4-AUDIO_FB)") (class "Default")
      (node (ref "R31") (pin "1") (pinfunction "1_1") (pintype "passive"))
      (node (ref "R32") (pin "1") (pinfunction "1_1") (pintype "passive"))
      (node (ref "R34") (pin "2") (pinfunction "2_2") (pintype "passive"))
      (node (ref "U4") (pin "7") (pinfunction "AUDIO_FB_7") (pintype "passive"))
    )
    (net (code "67") (name "Net-(U4-IF_AMP_IN)") (class "Default")
      (node (ref "U4") (pin "18") (pinfunction "IF_AMP_IN_18") (pintype "passive"))
      (node (ref "Y4") (pin "2") (pinfunction "Out_2") (pintype "passive"))
    )
    (net (code "68") (name "Net-(U4-IF_AMP_OUT)") (class "Default")
      (node (ref "R26") (pin "2") (pinfunction "2_2") (pintype "passive"))
      (node (ref "U4") (pin "16") (pinfunction "IF_AMP_OUT_16") (pintype "passive"))
    )
    (net (code "69") (name "Net-(U4-LIM_IN)") (class "Default")
      (node (ref "U4") (pin "14") (pinfunction "LIM_IN_14") (pintype "passive"))
      (node (ref "Y7") (pin "1") (pinfunction "In_1") (pintype "passive"))
    )
    (net (code "70") (name "Net-(U4-LIM_OUT_+)") (class "Default")
      (node (ref "C77") (pin "2") (pinfunction "2_2") (pintype "passive"))
      (node (ref "U4") (pin "11") (pinfunction "LIM_OUT_+_11") (pintype "passive"))
    )
    (net (code "71") (name "Net-(U4-MIX_OUT)") (class "Default")
      (node (ref "U4") (pin "20") (pinfunction "MIX_OUT_20") (pintype "passive"))
      (node (ref "Y4") (pin "1") (pinfunction "In_1") (pintype "passive"))
    )
    (net (code "72") (name "Net-(U4-OSC_IN)") (class "Default")
      (node (ref "C69") (pin "1") (pinfunction "1_1") (pintype "passive"))
      (node (ref "U4") (pin "4") (pinfunction "OSC_IN_4") (pintype "passive"))
      (node (ref "Y6") (pin "1") (pinfunction "OSC1_1") (pintype "passive"))
    )
    (net (code "73") (name "Net-(U4-OSC_OUT)") (class "Default")
      (node (ref "C68") (pin "2") (pinfunction "2_2") (pintype "passive"))
      (node (ref "C69") (pin "2") (pinfunction "2_2") (pintype "passive"))
      (node (ref "L16") (pin "2") (pinfunction "2_2") (pintype "passive"))
      (node (ref "U4") (pin "3") (pinfunction "OSC_OUT_3") (pintype "passive"))
    )
    (net (code "74") (name "Net-(U4-Q_IN)") (class "Default")
      (node (ref "C77") (pin "1") (pinfunction "1_1") (pintype "passive"))
      (node (ref "R36") (pin "1") (pinfunction "1_1") (pintype "passive"))
      (node (ref "U4") (pin "10") (pinfunction "Q_IN_10") (pintype "passive"))
      (node (ref "Y8") (pin "1") (pinfunction "OSC1_1") (pintype "passive"))
    )
    (net (code "75") (name "Net-(U4-RF_IN_+)") (class "Default")
      (node (ref "C1") (pin "2") (pinfunction "2_2") (pintype "passive"))
      (node (ref "R22") (pin "1") (pinfunction "1_1") (pintype "passive"))
      (node (ref "U4") (pin "1") (pinfunction "RF_IN_+_1") (pintype "passive"))
      (node (ref "Y3") (pin "3") (pinfunction "3_3") (pintype "passive"))
    )
    (net (code "76") (name "Net-(U4-RF_IN_-)") (class "Default")
      (node (ref "C60") (pin "2") (pinfunction "2_2") (pintype "passive"))
      (node (ref "R22") (pin "2") (pinfunction "2_2") (pintype "passive"))
      (node (ref "U4") (pin "2") (pinfunction "RF_IN_-_2") (pintype "passive"))
    )
    (net (code "77") (name "Net-(Y2-Out)") (class "Default")
      (node (ref "R1") (pin "2") (pinfunction "2_2") (pintype "passive"))
      (node (ref "R15") (pin "2") (pinfunction "2_2") (pintype "passive"))
      (node (ref "R2") (pin "2") (pinfunction "2_2") (pintype "passive"))
      (node (ref "Y2") (pin "3") (pinfunction "Out_3") (pintype "passive"))
    )
    (net (code "78") (name "Net-(Y2-Vcon)") (class "Default")
      (node (ref "C51") (pin "1") (pinfunction "1_1") (pintype "passive"))
      (node (ref "R16") (pin "2") (pinfunction "2_2") (pintype "passive"))
      (node (ref "R17") (pin "1") (pinfunction "1_1") (pintype "passive"))
      (node (ref "Y2") (pin "1") (pinfunction "Vcon_1") (pintype "passive"))
    )
    (net (code "79") (name "Net-(Y7-Out)") (class "Default")
      (node (ref "R26") (pin "1") (pinfunction "1_1") (pintype "passive"))
      (node (ref "R27") (pin "2") (pinfunction "2_2") (pintype "passive"))
      (node (ref "Y7") (pin "2") (pinfunction "Out_2") (pintype "passive"))
    )
    (net (code "80") (name "RFIN_GND") (class "Default")
      (node (ref "C1") (pin "1") (pinfunction "1_1") (pintype "passive"))
      (node (ref "C52") (pin "1") (pinfunction "1_1") (pintype "passive"))
      (node (ref "C53") (pin "1") (pinfunction "1_1") (pintype "passive"))
      (node (ref "C54") (pin "1") (pinfunction "1_1") (pintype "passive"))
      (node (ref "C55") (pin "1") (pinfunction "1_1") (pintype "passive"))
      (node (ref "C56") (pin "1") (pinfunction "1_1") (pintype "passive"))
      (node (ref "C57") (pin "2") (pinfunction "2_2") (pintype "passive"))
      (node (ref "C60") (pin "1") (pinfunction "1_1") (pintype "passive"))
      (node (ref "C62") (pin "2") (pinfunction "2_2") (pintype "passive"))
      (node (ref "C65") (pin "1") (pinfunction "1_1") (pintype "passive"))
      (node (ref "C66") (pin "2") (pinfunction "2_2") (pintype "passive"))
      (node (ref "C67") (pin "1") (pinfunction "1_1") (pintype "passive"))
      (node (ref "C68") (pin "1") (pinfunction "1_1") (pintype "passive"))
      (node (ref "C70") (pin "1") (pinfunction "1_1") (pintype "passive"))
      (node (ref "C71") (pin "1") (pinfunction "1_1") (pintype "passive"))
      (node (ref "C71") (pin "2") (pinfunction "2_2") (pintype "passive"))
      (node (ref "C72") (pin "1") (pinfunction "1_1") (pintype "passive"))
      (node (ref "C72") (pin "2") (pinfunction "2_2") (pintype "passive"))
      (node (ref "C74") (pin "1") (pinfunction "1_1") (pintype "passive"))
      (node (ref "C75") (pin "1") (pinfunction "1_1") (pintype "passive"))
      (node (ref "C76") (pin "1") (pinfunction "1_1") (pintype "passive"))
      (node (ref "C78") (pin "1") (pinfunction "1_1") (pintype "passive"))
      (node (ref "L1") (pin "1") (pinfunction "1_1") (pintype "passive"))
      (node (ref "L18") (pin "1") (pinfunction "1_1") (pintype "passive"))
      (node (ref "L19") (pin "1") (pinfunction "1_1") (pintype "passive"))
      (node (ref "L37") (pin "2") (pinfunction "2_2") (pintype "passive"))
      (node (ref "Q1") (pin "3") (pinfunction "S_3") (pintype "passive"))
      (node (ref "R28") (pin "2") (pinfunction "2_2") (pintype "passive"))
      (node (ref "R29") (pin "2") (pinfunction "2_2") (pintype "passive"))
      (node (ref "R34") (pin "1") (pinfunction "1_1") (pintype "passive"))
      (node (ref "U3") (pin "1") (pinfunction "GND_1") (pintype "passive"))
      (node (ref "U3") (pin "4") (pinfunction "GND_4") (pintype "passive"))
      (node (ref "U3") (pin "5") (pinfunction "GND_5") (pintype "passive"))
      (node (ref "U4") (pin "15") (pinfunction "GND_15") (pintype "passive"))
      (node (ref "Y3") (pin "2") (pinfunction "2_2") (pintype "passive"))
      (node (ref "Y4") (pin "3") (pinfunction "GND_3") (pintype "passive"))
      (node (ref "Y5") (pin "2") (pinfunction "2_2") (pintype "passive"))
      (node (ref "Y6") (pin "2") (pinfunction "OSC2_2") (pintype "passive"))
      (node (ref "Y7") (pin "3") (pinfunction "GND_3") (pintype "passive"))
      (node (ref "Y8") (pin "2") (pinfunction "OSC2_2") (pintype "passive"))
    )
    (net (code "81") (name "unconnected-(U2-ADCIN-Pad30)") (class "Default")
      (node (ref "U2") (pin "30") (pinfunction "ADCIN_30") (pintype "passive"))
    )
    (net (code "82") (name "unconnected-(U2-FLT_I-Pad17)") (class "Default")
      (node (ref "U2") (pin "17") (pinfunction "FLT_I_17") (pintype "passive+no_connect"))
    )
    (net (code "83") (name "unconnected-(U2-FLT_I-Pad18)") (class "Default")
      (node (ref "U2") (pin "18") (pinfunction "FLT_I_18") (pintype "passive+no_connect"))
    )
    (net (code "84") (name "unconnected-(U2-FLT_Q-Pad20)") (class "Default")
      (node (ref "U2") (pin "20") (pinfunction "FLT_Q_20") (pintype "passive+no_connect"))
    )
    (net (code "85") (name "unconnected-(U2-FLT_Q-Pad21)") (class "Default")
      (node (ref "U2") (pin "21") (pinfunction "FLT_Q_21") (pintype "passive+no_connect"))
    )
    (net (code "86") (name "unconnected-(U2-MIX_I-Pad13)") (class "Default")
      (node (ref "U2") (pin "13") (pinfunction "MIX_I_13") (pintype "passive+no_connect"))
    )
    (net (code "87") (name "unconnected-(U2-MIX_I-Pad14)") (class "Default")
      (node (ref "U2") (pin "14") (pinfunction "MIX_I_14") (pintype "passive+no_connect"))
    )
    (net (code "88") (name "unconnected-(U2-MIX_Q-Pad15)") (class "Default")
      (node (ref "U2") (pin "15") (pinfunction "MIX_Q_15") (pintype "passive+no_connect"))
    )
    (net (code "89") (name "unconnected-(U2-MIX_Q-Pad16)") (class "Default")
      (node (ref "U2") (pin "16") (pinfunction "MIX_Q_16") (pintype "passive+no_connect"))
    )
    (net (code "90") (name "unconnected-(U2-SWD-Pad33)") (class "Default")
      (node (ref "U2") (pin "33") (pinfunction "SWD_33") (pintype "passive+no_connect"))
    )
    (net (code "91") (name "unconnected-(U2-TEST_A-Pad23)") (class "Default")
      (node (ref "U2") (pin "23") (pinfunction "TEST_A_23") (pintype "passive+no_connect"))
    )
  )
)
